# MDrive.net
KiCad netlist of a schematic drawn in Altium Designer
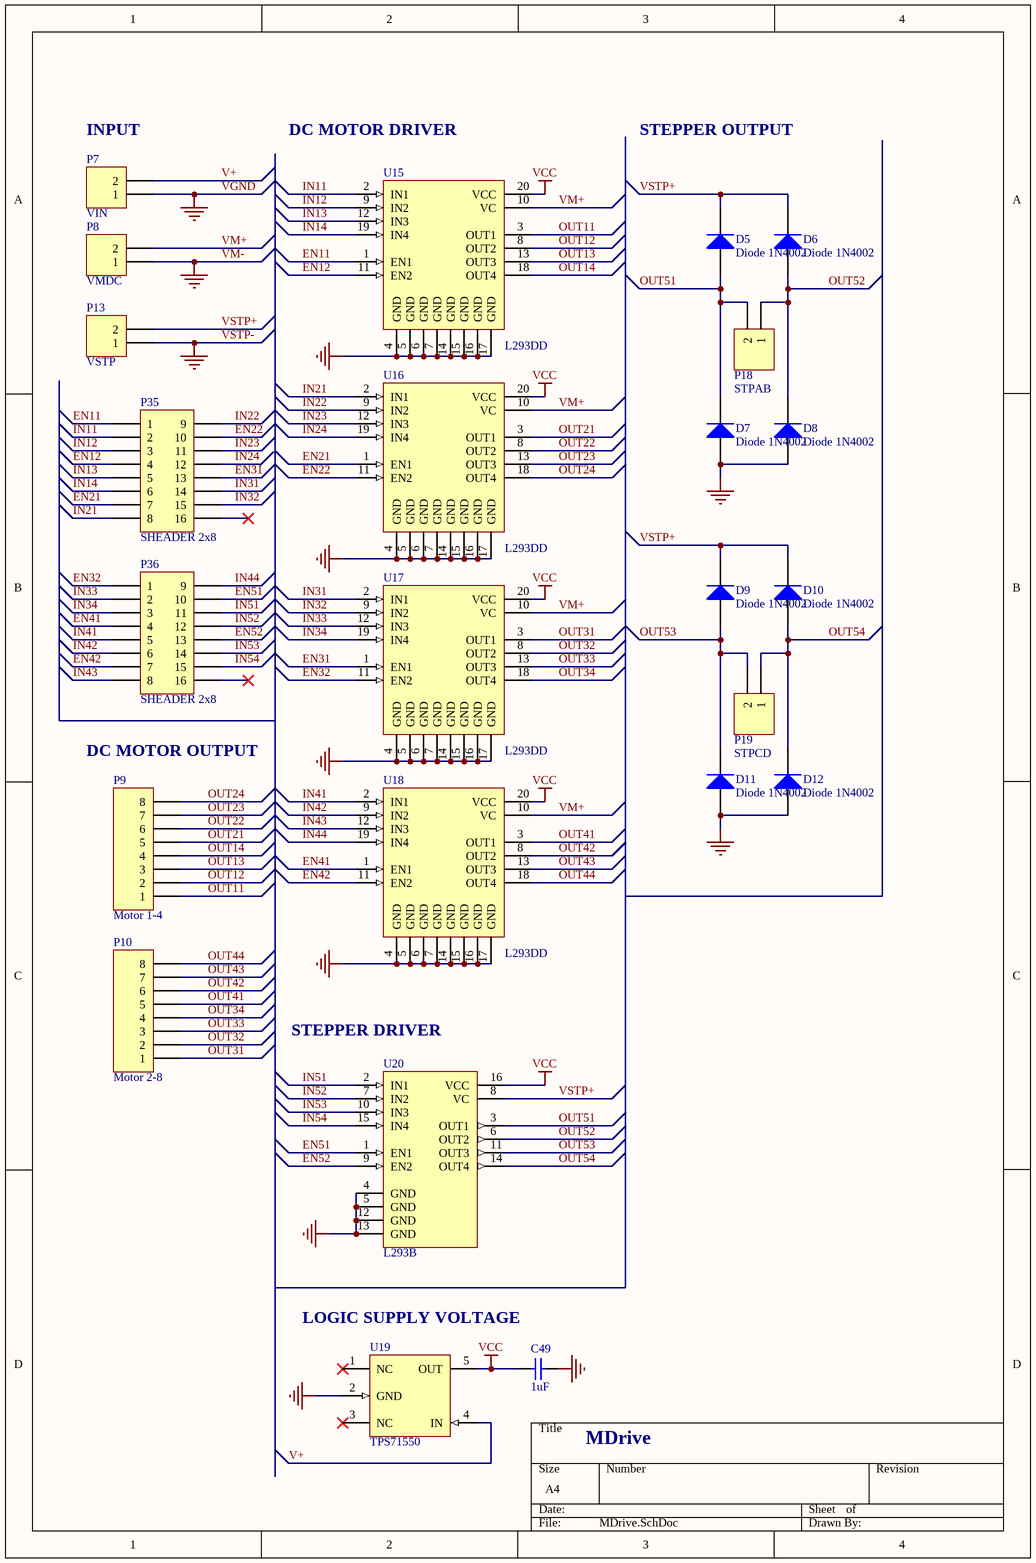
[diagram p0: MDrive.SchDoc]

(export (version "E")
  (design (tool "Eeschema 10.0.6"))
  (components
    (comp (ref "C49")
      (value "1uF")
      (footprint "CAPC2012M")
      (description "Capacitor (Semiconductor SIM Model)")
      (fields (field (name "Comment") "Cap Semi") (field (name "PUBLISHER") "Altium Limited"))
      (libsource (lib "Miscellaneous Devices") (part "Cap Semi"))
    )
    (comp (ref "D5")
      (value "Diode 1N4002")
      (footprint "DO-41")
      (description "1 Amp General Purpose Rectifier")
      (fields (field (name "PUBLISHER") "Altium Limited"))
      (libsource (lib "Miscellaneous Devices") (part "Diode 1N4002"))
    )
    (comp (ref "D6")
      (value "Diode 1N4002")
      (footprint "DO-41")
      (description "1 Amp General Purpose Rectifier")
      (fields (field (name "PUBLISHER") "Altium Limited"))
      (libsource (lib "Miscellaneous Devices") (part "Diode 1N4002"))
    )
    (comp (ref "D7")
      (value "Diode 1N4002")
      (footprint "DO-41")
      (description "1 Amp General Purpose Rectifier")
      (fields (field (name "PUBLISHER") "Altium Limited"))
      (libsource (lib "Miscellaneous Devices") (part "Diode 1N4002"))
    )
    (comp (ref "D8")
      (value "Diode 1N4002")
      (footprint "DO-41")
      (description "1 Amp General Purpose Rectifier")
      (fields (field (name "PUBLISHER") "Altium Limited"))
      (libsource (lib "Miscellaneous Devices") (part "Diode 1N4002"))
    )
    (comp (ref "D9")
      (value "Diode 1N4002")
      (footprint "DO-41")
      (description "1 Amp General Purpose Rectifier")
      (fields (field (name "PUBLISHER") "Altium Limited"))
      (libsource (lib "Miscellaneous Devices") (part "Diode 1N4002"))
    )
    (comp (ref "D10")
      (value "Diode 1N4002")
      (footprint "DO-41")
      (description "1 Amp General Purpose Rectifier")
      (fields (field (name "PUBLISHER") "Altium Limited"))
      (libsource (lib "Miscellaneous Devices") (part "Diode 1N4002"))
    )
    (comp (ref "D11")
      (value "Diode 1N4002")
      (footprint "DO-41")
      (description "1 Amp General Purpose Rectifier")
      (fields (field (name "PUBLISHER") "Altium Limited"))
      (libsource (lib "Miscellaneous Devices") (part "Diode 1N4002"))
    )
    (comp (ref "D12")
      (value "Diode 1N4002")
      (footprint "DO-41")
      (description "1 Amp General Purpose Rectifier")
      (fields (field (name "PUBLISHER") "Altium Limited"))
      (libsource (lib "Miscellaneous Devices") (part "Diode 1N4002"))
    )
    (comp (ref "P7")
      (value "VIN")
      (footprint "AZUL5-2")
      (description "Header, 2-Pin")
      (fields (field (name "PUBLISHER") "Altium Limited"))
      (libsource (lib "Miscellaneous Connectors") (part "Header 2"))
    )
    (comp (ref "P8")
      (value "VMDC")
      (footprint "AZUL5-2")
      (description "Header, 2-Pin")
      (fields (field (name "PUBLISHER") "Altium Limited"))
      (libsource (lib "Miscellaneous Connectors") (part "Header 2"))
    )
    (comp (ref "P9")
      (value "Motor 1-4")
      (footprint "AZUL5-8")
      (description "Header, 8-Pin")
      (fields (field (name "PUBLISHER") "Altium Limited"))
      (libsource (lib "Miscellaneous Connectors") (part "Header 8"))
    )
    (comp (ref "P10")
      (value "Motor 2-8")
      (footprint "AZUL5-8")
      (description "Header, 8-Pin")
      (fields (field (name "PUBLISHER") "Altium Limited"))
      (libsource (lib "Miscellaneous Connectors") (part "Header 8"))
    )
    (comp (ref "P13")
      (value "VSTP")
      (footprint "AZUL5-2")
      (description "Header, 2-Pin")
      (fields (field (name "PUBLISHER") "Altium Limited"))
      (libsource (lib "Miscellaneous Connectors") (part "Header 2"))
    )
    (comp (ref "P18")
      (value "STPAB")
      (footprint "AZUL5-2")
      (description "Header, 2-Pin")
      (fields (field (name "PUBLISHER") "Altium Limited"))
      (libsource (lib "") (part "Header 2_1"))
    )
    (comp (ref "P19")
      (value "STPCD")
      (footprint "AZUL5-2")
      (description "Header, 2-Pin")
      (fields (field (name "PUBLISHER") "Altium Limited"))
      (libsource (lib "") (part "Header 2_1"))
    )
    (comp (ref "P35")
      (value "SHEADER 2x8")
      (footprint "SHBH 2X8")
      (description "Shrouded Box Header: 2x8-Pin, 0.100\" (2.54 mm) Male")
      (libsource (lib "LitoLibrary") (part "SB Header 2x8"))
    )
    (comp (ref "P36")
      (value "SHEADER 2x8")
      (footprint "SHBH 2X8")
      (description "Shrouded Box Header: 2x8-Pin, 0.100\" (2.54 mm) Male")
      (libsource (lib "LitoLibrary") (part "SB Header 2x8"))
    )
    (comp (ref "U15")
      (value "L293DD")
      (footprint "SO20_N")
      (description "Push-Pull Four Channel Driver With Diode")
      (fields (field (name "PUBLISHER") "Altium Limited"))
      (libsource (lib "ST Interface DC & Stepper Motor Controller") (part "L293DD"))
    )
    (comp (ref "U16")
      (value "L293DD")
      (footprint "SO20_N")
      (description "Push-Pull Four Channel Driver With Diode")
      (fields (field (name "PUBLISHER") "Altium Limited"))
      (libsource (lib "ST Interface DC & Stepper Motor Controller") (part "L293DD"))
    )
    (comp (ref "U17")
      (value "L293DD")
      (footprint "SO20_N")
      (description "Push-Pull Four Channel Driver With Diode")
      (fields (field (name "PUBLISHER") "Altium Limited"))
      (libsource (lib "ST Interface DC & Stepper Motor Controller") (part "L293DD"))
    )
    (comp (ref "U18")
      (value "L293DD")
      (footprint "SO20_N")
      (description "Push-Pull Four Channel Driver With Diode")
      (fields (field (name "PUBLISHER") "Altium Limited"))
      (libsource (lib "ST Interface DC & Stepper Motor Controller") (part "L293DD"))
    )
    (comp (ref "U19")
      (value "TPS71550")
      (footprint "SOT353-5L")
      (libsource (lib "LitoLibrary") (part "TPS71550"))
    )
    (comp (ref "U20")
      (value "L293B")
      (footprint "DIP16")
      (description "Push-Pull Four Channel Drivers")
      (fields (field (name "PUBLISHER") "Altium Limited"))
      (libsource (lib "ST Interface DC & Stepper Motor Controller") (part "L293B"))
    )
  )
  (nets
    (net (code "1") (name "/EN11") (class "Default")
      (node (ref "P35") (pin "1") (pinfunction "1_1") (pintype "passive"))
      (node (ref "U15") (pin "1") (pinfunction "EN1_1") (pintype "input"))
    )
    (net (code "2") (name "/EN12") (class "Default")
      (node (ref "P35") (pin "4") (pinfunction "4_4") (pintype "passive"))
      (node (ref "U15") (pin "11") (pinfunction "EN2_11") (pintype "input"))
    )
    (net (code "3") (name "/EN21") (class "Default")
      (node (ref "P35") (pin "7") (pinfunction "7_7") (pintype "passive"))
      (node (ref "U16") (pin "1") (pinfunction "EN1_1") (pintype "input"))
    )
    (net (code "4") (name "/EN22") (class "Default")
      (node (ref "P35") (pin "10") (pinfunction "10_10") (pintype "passive"))
      (node (ref "U16") (pin "11") (pinfunction "EN2_11") (pintype "input"))
    )
    (net (code "5") (name "/EN31") (class "Default")
      (node (ref "P35") (pin "13") (pinfunction "13_13") (pintype "passive"))
      (node (ref "U17") (pin "1") (pinfunction "EN1_1") (pintype "input"))
    )
    (net (code "6") (name "/EN32") (class "Default")
      (node (ref "P36") (pin "1") (pinfunction "1_1") (pintype "passive"))
      (node (ref "U17") (pin "11") (pinfunction "EN2_11") (pintype "input"))
    )
    (net (code "7") (name "/EN41") (class "Default")
      (node (ref "P36") (pin "4") (pinfunction "4_4") (pintype "passive"))
      (node (ref "U18") (pin "1") (pinfunction "EN1_1") (pintype "input"))
    )
    (net (code "8") (name "/EN42") (class "Default")
      (node (ref "P36") (pin "7") (pinfunction "7_7") (pintype "passive"))
      (node (ref "U18") (pin "11") (pinfunction "EN2_11") (pintype "input"))
    )
    (net (code "9") (name "/EN51") (class "Default")
      (node (ref "P36") (pin "10") (pinfunction "10_10") (pintype "passive"))
      (node (ref "U20") (pin "1") (pinfunction "EN1_1") (pintype "input"))
    )
    (net (code "10") (name "/EN52") (class "Default")
      (node (ref "P36") (pin "13") (pinfunction "13_13") (pintype "passive"))
      (node (ref "U20") (pin "9") (pinfunction "EN2_9") (pintype "input"))
    )
    (net (code "11") (name "/IN11") (class "Default")
      (node (ref "P35") (pin "2") (pinfunction "2_2") (pintype "passive"))
      (node (ref "U15") (pin "2") (pinfunction "IN1_2") (pintype "input"))
    )
    (net (code "12") (name "/IN12") (class "Default")
      (node (ref "P35") (pin "3") (pinfunction "3_3") (pintype "passive"))
      (node (ref "U15") (pin "9") (pinfunction "IN2_9") (pintype "input"))
    )
    (net (code "13") (name "/IN13") (class "Default")
      (node (ref "P35") (pin "5") (pinfunction "5_5") (pintype "passive"))
      (node (ref "U15") (pin "12") (pinfunction "IN3_12") (pintype "input"))
    )
    (net (code "14") (name "/IN14") (class "Default")
      (node (ref "P35") (pin "6") (pinfunction "6_6") (pintype "passive"))
      (node (ref "U15") (pin "19") (pinfunction "IN4_19") (pintype "input"))
    )
    (net (code "15") (name "/IN21") (class "Default")
      (node (ref "P35") (pin "8") (pinfunction "8_8") (pintype "passive"))
      (node (ref "U16") (pin "2") (pinfunction "IN1_2") (pintype "input"))
    )
    (net (code "16") (name "/IN22") (class "Default")
      (node (ref "P35") (pin "9") (pinfunction "9_9") (pintype "passive"))
      (node (ref "U16") (pin "9") (pinfunction "IN2_9") (pintype "input"))
    )
    (net (code "17") (name "/IN23") (class "Default")
      (node (ref "P35") (pin "11") (pinfunction "11_11") (pintype "passive"))
      (node (ref "U16") (pin "12") (pinfunction "IN3_12") (pintype "input"))
    )
    (net (code "18") (name "/IN24") (class "Default")
      (node (ref "P35") (pin "12") (pinfunction "12_12") (pintype "passive"))
      (node (ref "U16") (pin "19") (pinfunction "IN4_19") (pintype "input"))
    )
    (net (code "19") (name "/IN31") (class "Default")
      (node (ref "P35") (pin "14") (pinfunction "14_14") (pintype "passive"))
      (node (ref "U17") (pin "2") (pinfunction "IN1_2") (pintype "input"))
    )
    (net (code "20") (name "/IN32") (class "Default")
      (node (ref "P35") (pin "15") (pinfunction "15_15") (pintype "passive"))
      (node (ref "U17") (pin "9") (pinfunction "IN2_9") (pintype "input"))
    )
    (net (code "21") (name "/IN33") (class "Default")
      (node (ref "P36") (pin "2") (pinfunction "2_2") (pintype "passive"))
      (node (ref "U17") (pin "12") (pinfunction "IN3_12") (pintype "input"))
    )
    (net (code "22") (name "/IN34") (class "Default")
      (node (ref "P36") (pin "3") (pinfunction "3_3") (pintype "passive"))
      (node (ref "U17") (pin "19") (pinfunction "IN4_19") (pintype "input"))
    )
    (net (code "23") (name "/IN41") (class "Default")
      (node (ref "P36") (pin "5") (pinfunction "5_5") (pintype "passive"))
      (node (ref "U18") (pin "2") (pinfunction "IN1_2") (pintype "input"))
    )
    (net (code "24") (name "/IN42") (class "Default")
      (node (ref "P36") (pin "6") (pinfunction "6_6") (pintype "passive"))
      (node (ref "U18") (pin "9") (pinfunction "IN2_9") (pintype "input"))
    )
    (net (code "25") (name "/IN43") (class "Default")
      (node (ref "P36") (pin "8") (pinfunction "8_8") (pintype "passive"))
      (node (ref "U18") (pin "12") (pinfunction "IN3_12") (pintype "input"))
    )
    (net (code "26") (name "/IN44") (class "Default")
      (node (ref "P36") (pin "9") (pinfunction "9_9") (pintype "passive"))
      (node (ref "U18") (pin "19") (pinfunction "IN4_19") (pintype "input"))
    )
    (net (code "27") (name "/IN51") (class "Default")
      (node (ref "P36") (pin "11") (pinfunction "11_11") (pintype "passive"))
      (node (ref "U20") (pin "2") (pinfunction "IN1_2") (pintype "input"))
    )
    (net (code "28") (name "/IN52") (class "Default")
      (node (ref "P36") (pin "12") (pinfunction "12_12") (pintype "passive"))
      (node (ref "U20") (pin "7") (pinfunction "IN2_7") (pintype "input"))
    )
    (net (code "29") (name "/IN53") (class "Default")
      (node (ref "P36") (pin "14") (pinfunction "14_14") (pintype "passive"))
      (node (ref "U20") (pin "10") (pinfunction "IN3_10") (pintype "input"))
    )
    (net (code "30") (name "/IN54") (class "Default")
      (node (ref "P36") (pin "15") (pinfunction "15_15") (pintype "passive"))
      (node (ref "U20") (pin "15") (pinfunction "IN4_15") (pintype "input"))
    )
    (net (code "31") (name "/OUT11") (class "Default")
      (node (ref "P9") (pin "1") (pinfunction "1_1") (pintype "passive"))
      (node (ref "U15") (pin "3") (pinfunction "OUT1_3") (pintype "tri_state"))
    )
    (net (code "32") (name "/OUT12") (class "Default")
      (node (ref "P9") (pin "2") (pinfunction "2_2") (pintype "passive"))
      (node (ref "U15") (pin "8") (pinfunction "OUT2_8") (pintype "tri_state"))
    )
    (net (code "33") (name "/OUT13") (class "Default")
      (node (ref "P9") (pin "3") (pinfunction "3_3") (pintype "passive"))
      (node (ref "U15") (pin "13") (pinfunction "OUT3_13") (pintype "tri_state"))
    )
    (net (code "34") (name "/OUT14") (class "Default")
      (node (ref "P9") (pin "4") (pinfunction "4_4") (pintype "passive"))
      (node (ref "U15") (pin "18") (pinfunction "OUT4_18") (pintype "tri_state"))
    )
    (net (code "35") (name "/OUT21") (class "Default")
      (node (ref "P9") (pin "5") (pinfunction "5_5") (pintype "passive"))
      (node (ref "U16") (pin "3") (pinfunction "OUT1_3") (pintype "tri_state"))
    )
    (net (code "36") (name "/OUT22") (class "Default")
      (node (ref "P9") (pin "6") (pinfunction "6_6") (pintype "passive"))
      (node (ref "U16") (pin "8") (pinfunction "OUT2_8") (pintype "tri_state"))
    )
    (net (code "37") (name "/OUT23") (class "Default")
      (node (ref "P9") (pin "7") (pinfunction "7_7") (pintype "passive"))
      (node (ref "U16") (pin "13") (pinfunction "OUT3_13") (pintype "tri_state"))
    )
    (net (code "38") (name "/OUT24") (class "Default")
      (node (ref "P9") (pin "8") (pinfunction "8_8") (pintype "passive"))
      (node (ref "U16") (pin "18") (pinfunction "OUT4_18") (pintype "tri_state"))
    )
    (net (code "39") (name "/OUT31") (class "Default")
      (node (ref "P10") (pin "1") (pinfunction "1_1") (pintype "passive"))
      (node (ref "U17") (pin "3") (pinfunction "OUT1_3") (pintype "tri_state"))
    )
    (net (code "40") (name "/OUT32") (class "Default")
      (node (ref "P10") (pin "2") (pinfunction "2_2") (pintype "passive"))
      (node (ref "U17") (pin "8") (pinfunction "OUT2_8") (pintype "tri_state"))
    )
    (net (code "41") (name "/OUT33") (class "Default")
      (node (ref "P10") (pin "3") (pinfunction "3_3") (pintype "passive"))
      (node (ref "U17") (pin "13") (pinfunction "OUT3_13") (pintype "tri_state"))
    )
    (net (code "42") (name "/OUT34") (class "Default")
      (node (ref "P10") (pin "4") (pinfunction "4_4") (pintype "passive"))
      (node (ref "U17") (pin "18") (pinfunction "OUT4_18") (pintype "tri_state"))
    )
    (net (code "43") (name "/OUT41") (class "Default")
      (node (ref "P10") (pin "5") (pinfunction "5_5") (pintype "passive"))
      (node (ref "U18") (pin "3") (pinfunction "OUT1_3") (pintype "tri_state"))
    )
    (net (code "44") (name "/OUT42") (class "Default")
      (node (ref "P10") (pin "6") (pinfunction "6_6") (pintype "passive"))
      (node (ref "U18") (pin "8") (pinfunction "OUT2_8") (pintype "tri_state"))
    )
    (net (code "45") (name "/OUT43") (class "Default")
      (node (ref "P10") (pin "7") (pinfunction "7_7") (pintype "passive"))
      (node (ref "U18") (pin "13") (pinfunction "OUT3_13") (pintype "tri_state"))
    )
    (net (code "46") (name "/OUT44") (class "Default")
      (node (ref "P10") (pin "8") (pinfunction "8_8") (pintype "passive"))
      (node (ref "U18") (pin "18") (pinfunction "OUT4_18") (pintype "tri_state"))
    )
    (net (code "47") (name "/OUT51") (class "Default")
      (node (ref "D5") (pin "1") (pinfunction "A_1") (pintype "passive"))
      (node (ref "D7") (pin "2") (pinfunction "K_2") (pintype "passive"))
      (node (ref "P18") (pin "2") (pinfunction "2_2") (pintype "passive"))
      (node (ref "U20") (pin "3") (pinfunction "OUT1_3") (pintype "output"))
    )
    (net (code "48") (name "/OUT52") (class "Default")
      (node (ref "D6") (pin "1") (pinfunction "A_1") (pintype "passive"))
      (node (ref "D8") (pin "2") (pinfunction "K_2") (pintype "passive"))
      (node (ref "P18") (pin "1") (pinfunction "1_1") (pintype "passive"))
      (node (ref "U20") (pin "6") (pinfunction "OUT2_6") (pintype "output"))
    )
    (net (code "49") (name "/OUT53") (class "Default")
      (node (ref "D11") (pin "2") (pinfunction "K_2") (pintype "passive"))
      (node (ref "D9") (pin "1") (pinfunction "A_1") (pintype "passive"))
      (node (ref "P19") (pin "2") (pinfunction "2_2") (pintype "passive"))
      (node (ref "U20") (pin "11") (pinfunction "OUT3_11") (pintype "output"))
    )
    (net (code "50") (name "/OUT54") (class "Default")
      (node (ref "D10") (pin "1") (pinfunction "A_1") (pintype "passive"))
      (node (ref "D12") (pin "2") (pinfunction "K_2") (pintype "passive"))
      (node (ref "P19") (pin "1") (pinfunction "1_1") (pintype "passive"))
      (node (ref "U20") (pin "14") (pinfunction "OUT4_14") (pintype "output"))
    )
    (net (code "51") (name "/V+") (class "Default")
      (node (ref "P7") (pin "2") (pinfunction "2_2") (pintype "passive"))
      (node (ref "U19") (pin "4") (pinfunction "IN_4") (pintype "input"))
    )
    (net (code "52") (name "/VM+") (class "Default")
      (node (ref "P8") (pin "2") (pinfunction "2_2") (pintype "passive"))
      (node (ref "U15") (pin "10") (pinfunction "VC_10") (pintype "power_in"))
      (node (ref "U16") (pin "10") (pinfunction "VC_10") (pintype "power_in"))
      (node (ref "U17") (pin "10") (pinfunction "VC_10") (pintype "power_in"))
      (node (ref "U18") (pin "10") (pinfunction "VC_10") (pintype "power_in"))
    )
    (net (code "53") (name "/VSTP+") (class "Default")
      (node (ref "D10") (pin "2") (pinfunction "K_2") (pintype "passive"))
      (node (ref "D5") (pin "2") (pinfunction "K_2") (pintype "passive"))
      (node (ref "D6") (pin "2") (pinfunction "K_2") (pintype "passive"))
      (node (ref "D9") (pin "2") (pinfunction "K_2") (pintype "passive"))
      (node (ref "P13") (pin "2") (pinfunction "2_2") (pintype "passive"))
      (node (ref "U20") (pin "8") (pinfunction "VC_8") (pintype "power_in"))
    )
    (net (code "54") (name "GND") (class "Default")
      (node (ref "C49") (pin "2") (pinfunction "2_2") (pintype "passive"))
      (node (ref "D11") (pin "1") (pinfunction "A_1") (pintype "passive"))
      (node (ref "D12") (pin "1") (pinfunction "A_1") (pintype "passive"))
      (node (ref "D7") (pin "1") (pinfunction "A_1") (pintype "passive"))
      (node (ref "D8") (pin "1") (pinfunction "A_1") (pintype "passive"))
      (node (ref "P13") (pin "1") (pinfunction "1_1") (pintype "passive"))
      (node (ref "P7") (pin "1") (pinfunction "1_1") (pintype "passive"))
      (node (ref "P8") (pin "1") (pinfunction "1_1") (pintype "passive"))
      (node (ref "U15") (pin "14") (pinfunction "GND_14") (pintype "power_in"))
      (node (ref "U15") (pin "15") (pinfunction "GND_15") (pintype "power_in"))
      (node (ref "U15") (pin "16") (pinfunction "GND_16") (pintype "power_in"))
      (node (ref "U15") (pin "17") (pinfunction "GND_17") (pintype "power_in"))
      (node (ref "U15") (pin "4") (pinfunction "GND_4") (pintype "power_in"))
      (node (ref "U15") (pin "5") (pinfunction "GND_5") (pintype "power_in"))
      (node (ref "U15") (pin "6") (pinfunction "GND_6") (pintype "power_in"))
      (node (ref "U15") (pin "7") (pinfunction "GND_7") (pintype "power_in"))
      (node (ref "U16") (pin "14") (pinfunction "GND_14") (pintype "power_in"))
      (node (ref "U16") (pin "15") (pinfunction "GND_15") (pintype "power_in"))
      (node (ref "U16") (pin "16") (pinfunction "GND_16") (pintype "power_in"))
      (node (ref "U16") (pin "17") (pinfunction "GND_17") (pintype "power_in"))
      (node (ref "U16") (pin "4") (pinfunction "GND_4") (pintype "power_in"))
      (node (ref "U16") (pin "5") (pinfunction "GND_5") (pintype "power_in"))
      (node (ref "U16") (pin "6") (pinfunction "GND_6") (pintype "power_in"))
      (node (ref "U16") (pin "7") (pinfunction "GND_7") (pintype "power_in"))
      (node (ref "U17") (pin "14") (pinfunction "GND_14") (pintype "power_in"))
      (node (ref "U17") (pin "15") (pinfunction "GND_15") (pintype "power_in"))
      (node (ref "U17") (pin "16") (pinfunction "GND_16") (pintype "power_in"))
      (node (ref "U17") (pin "17") (pinfunction "GND_17") (pintype "power_in"))
      (node (ref "U17") (pin "4") (pinfunction "GND_4") (pintype "power_in"))
      (node (ref "U17") (pin "5") (pinfunction "GND_5") (pintype "power_in"))
      (node (ref "U17") (pin "6") (pinfunction "GND_6") (pintype "power_in"))
      (node (ref "U17") (pin "7") (pinfunction "GND_7") (pintype "power_in"))
      (node (ref "U18") (pin "14") (pinfunction "GND_14") (pintype "power_in"))
      (node (ref "U18") (pin "15") (pinfunction "GND_15") (pintype "power_in"))
      (node (ref "U18") (pin "16") (pinfunction "GND_16") (pintype "power_in"))
      (node (ref "U18") (pin "17") (pinfunction "GND_17") (pintype "power_in"))
      (node (ref "U18") (pin "4") (pinfunction "GND_4") (pintype "power_in"))
      (node (ref "U18") (pin "5") (pinfunction "GND_5") (pintype "power_in"))
      (node (ref "U18") (pin "6") (pinfunction "GND_6") (pintype "power_in"))
      (node (ref "U18") (pin "7") (pinfunction "GND_7") (pintype "power_in"))
      (node (ref "U19") (pin "2") (pinfunction "GND_2") (pintype "input"))
      (node (ref "U20") (pin "12") (pinfunction "GND_12") (pintype "power_in"))
      (node (ref "U20") (pin "13") (pinfunction "GND_13") (pintype "power_in"))
      (node (ref "U20") (pin "4") (pinfunction "GND_4") (pintype "power_in"))
      (node (ref "U20") (pin "5") (pinfunction "GND_5") (pintype "power_in"))
    )
    (net (code "55") (name "VCC") (class "Default")
      (node (ref "C49") (pin "1") (pinfunction "1_1") (pintype "passive"))
      (node (ref "U15") (pin "20") (pinfunction "VCC_20") (pintype "power_in"))
      (node (ref "U16") (pin "20") (pinfunction "VCC_20") (pintype "power_in"))
      (node (ref "U17") (pin "20") (pinfunction "VCC_20") (pintype "power_in"))
      (node (ref "U18") (pin "20") (pinfunction "VCC_20") (pintype "power_in"))
      (node (ref "U19") (pin "5") (pinfunction "OUT_5") (pintype "passive"))
      (node (ref "U20") (pin "16") (pinfunction "VCC_16") (pintype "power_in"))
    )
    (net (code "56") (name "unconnected-(P35-Pad16)") (class "Default")
      (node (ref "P35") (pin "16") (pinfunction "16_16") (pintype "passive+no_connect"))
    )
    (net (code "57") (name "unconnected-(P36-Pad16)") (class "Default")
      (node (ref "P36") (pin "16") (pinfunction "16_16") (pintype "passive+no_connect"))
    )
    (net (code "58") (name "unconnected-(U19-NC-Pad1)") (class "Default")
      (node (ref "U19") (pin "1") (pinfunction "NC_1") (pintype "passive+no_connect"))
    )
    (net (code "59") (name "unconnected-(U19-NC-Pad3)") (class "Default")
      (node (ref "U19") (pin "3") (pinfunction "NC_3") (pintype "passive+no_connect"))
    )
  )
)
